# Sheet1_MB.net
KiCad netlist of a schematic drawn in Altium Designer
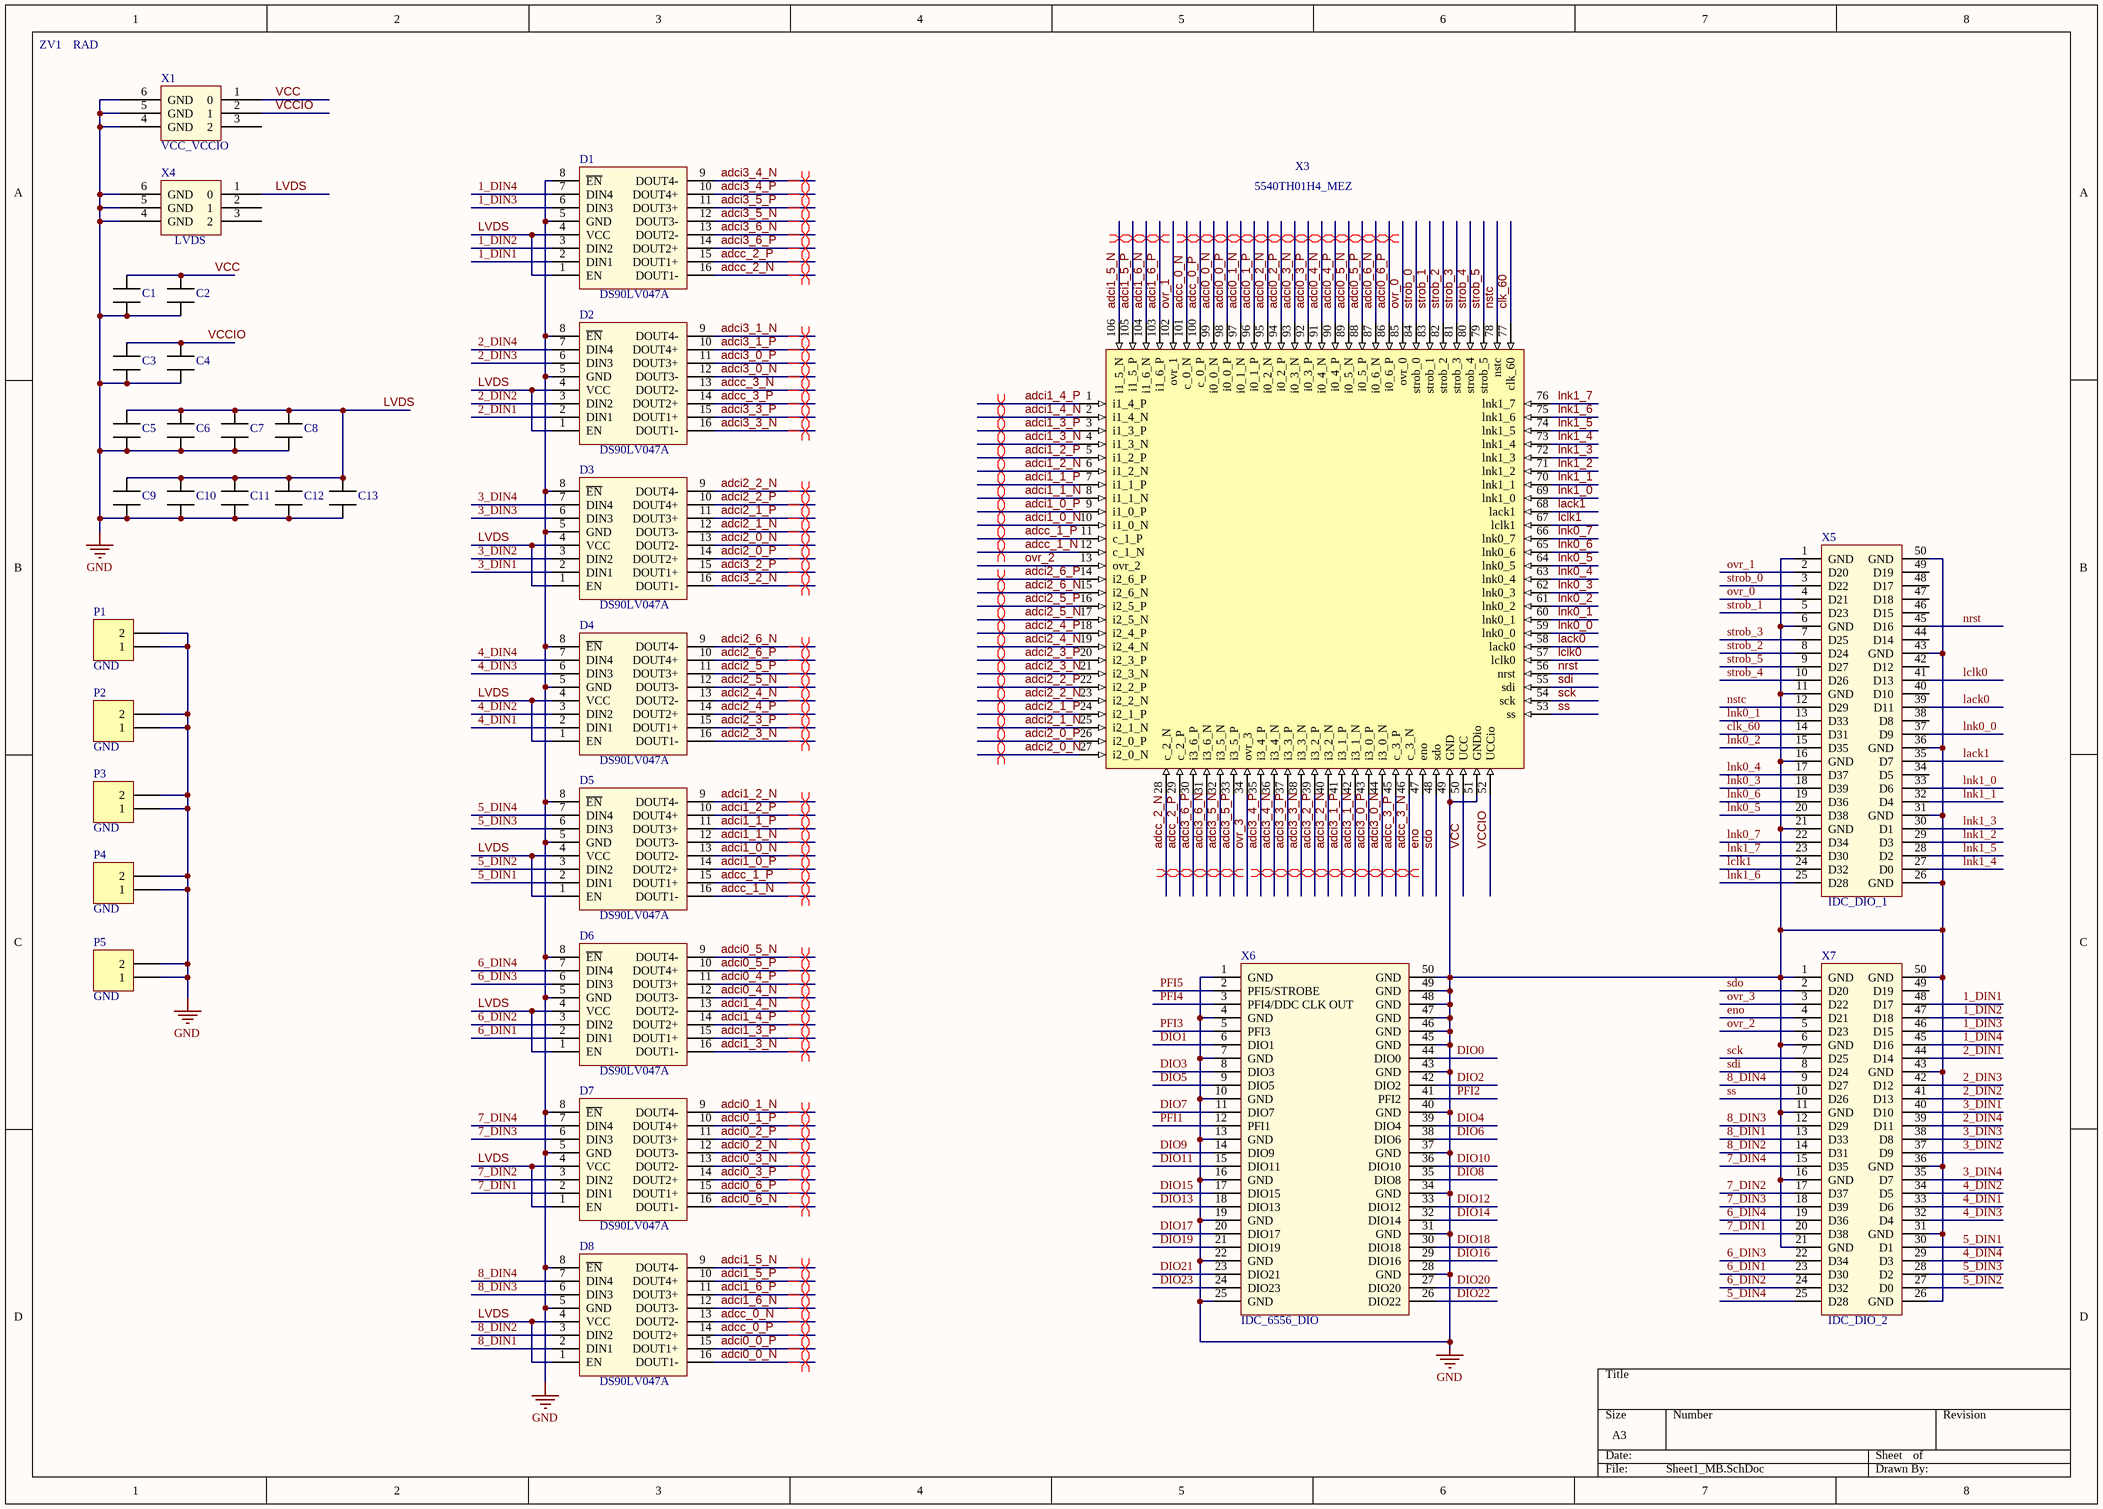
[diagram p0: Sheet1_MB.SchDoc]

(export (version "E")
  (design (tool "Eeschema 10.0.6"))
  (components
    (comp (ref "C1") (value "CAP_BIG") (footprint "Cap_BIG") (libsource (lib "Schlib") (part "CAP_BIG")))
    (comp (ref "C2")
      (value "CAP_SMALL")
      (footprint "CAP_SMALL")
      (libsource (lib "Schlib") (part "CAP_SMALL"))
    )
    (comp (ref "C3") (value "CAP_BIG") (footprint "Cap_BIG") (libsource (lib "Schlib") (part "CAP_BIG")))
    (comp (ref "C4")
      (value "CAP_SMALL")
      (footprint "CAP_SMALL")
      (libsource (lib "Schlib") (part "CAP_SMALL"))
    )
    (comp (ref "C5") (value "CAP_BIG") (footprint "Cap_BIG") (libsource (lib "Schlib") (part "CAP_BIG")))
    (comp (ref "C6")
      (value "CAP_SMALL")
      (footprint "CAP_SMALL")
      (libsource (lib "Schlib") (part "CAP_SMALL"))
    )
    (comp (ref "C7")
      (value "CAP_SMALL")
      (footprint "CAP_SMALL")
      (libsource (lib "Schlib") (part "CAP_SMALL"))
    )
    (comp (ref "C8")
      (value "CAP_SMALL")
      (footprint "CAP_SMALL")
      (libsource (lib "Schlib") (part "CAP_SMALL"))
    )
    (comp (ref "C9")
      (value "CAP_SMALL")
      (footprint "CAP_SMALL")
      (libsource (lib "Schlib") (part "CAP_SMALL"))
    )
    (comp (ref "C10")
      (value "CAP_SMALL")
      (footprint "CAP_SMALL")
      (libsource (lib "Schlib") (part "CAP_SMALL"))
    )
    (comp (ref "C11")
      (value "CAP_SMALL")
      (footprint "CAP_SMALL")
      (libsource (lib "Schlib") (part "CAP_SMALL"))
    )
    (comp (ref "C12")
      (value "CAP_SMALL")
      (footprint "CAP_SMALL")
      (libsource (lib "Schlib") (part "CAP_SMALL"))
    )
    (comp (ref "C13")
      (value "CAP_SMALL")
      (footprint "CAP_SMALL")
      (libsource (lib "Schlib") (part "CAP_SMALL"))
    )
    (comp (ref "D1")
      (value "DS90LV047A")
      (footprint "TSOP65P640X120-16N")
      (libsource (lib "Schlib") (part "DS90LV047A"))
    )
    (comp (ref "D2")
      (value "DS90LV047A")
      (footprint "TSOP65P640X120-16N")
      (libsource (lib "Schlib") (part "DS90LV047A"))
    )
    (comp (ref "D3")
      (value "DS90LV047A")
      (footprint "TSOP65P640X120-16N")
      (libsource (lib "Schlib") (part "DS90LV047A"))
    )
    (comp (ref "D4")
      (value "DS90LV047A")
      (footprint "TSOP65P640X120-16N")
      (libsource (lib "Schlib") (part "DS90LV047A"))
    )
    (comp (ref "D5")
      (value "DS90LV047A")
      (footprint "TSOP65P640X120-16N")
      (libsource (lib "Schlib") (part "DS90LV047A"))
    )
    (comp (ref "D6")
      (value "DS90LV047A")
      (footprint "TSOP65P640X120-16N")
      (libsource (lib "Schlib") (part "DS90LV047A"))
    )
    (comp (ref "D7")
      (value "DS90LV047A")
      (footprint "TSOP65P640X120-16N")
      (libsource (lib "Schlib") (part "DS90LV047A"))
    )
    (comp (ref "D8")
      (value "DS90LV047A")
      (footprint "TSOP65P640X120-16N")
      (libsource (lib "Schlib") (part "DS90LV047A"))
    )
    (comp (ref "P1")
      (value "GND")
      (footprint "HDR1X2")
      (description "Header, 2-Pin")
      (fields (field (name "PUBLISHER") "Altium Limited"))
      (libsource (lib "Miscellaneous Connectors") (part "Header 2"))
    )
    (comp (ref "P2")
      (value "GND")
      (footprint "HDR1X2")
      (description "Header, 2-Pin")
      (fields (field (name "PUBLISHER") "Altium Limited"))
      (libsource (lib "Miscellaneous Connectors") (part "Header 2"))
    )
    (comp (ref "P3")
      (value "GND")
      (footprint "HDR1X2")
      (description "Header, 2-Pin")
      (fields (field (name "PUBLISHER") "Altium Limited"))
      (libsource (lib "Miscellaneous Connectors") (part "Header 2"))
    )
    (comp (ref "P4")
      (value "GND")
      (footprint "HDR1X2")
      (description "Header, 2-Pin")
      (fields (field (name "PUBLISHER") "Altium Limited"))
      (libsource (lib "Miscellaneous Connectors") (part "Header 2"))
    )
    (comp (ref "P5")
      (value "GND")
      (footprint "HDR1X2")
      (description "Header, 2-Pin")
      (fields (field (name "PUBLISHER") "Altium Limited"))
      (libsource (lib "Miscellaneous Connectors") (part "Header 2"))
    )
    (comp (ref "X1") (value "VCC_VCCIO") (footprint "POWER") (libsource (lib "Schlib") (part "POWER")))
    (comp (ref "X3")
      (value "5540TH01H4_MEZ")
      (footprint "5540TH01H4_MEZ")
      (libsource (lib "VPL") (part "5540TH01H4_MEZ"))
    )
    (comp (ref "X4") (value "LVDS") (footprint "POWER") (libsource (lib "Schlib") (part "POWER")))
    (comp (ref "X5") (value "IDC_DIO_1") (footprint "IDC_DIO") (libsource (lib "VPL") (part "IDC_DIO")))
    (comp (ref "X6")
      (value "IDC_6556_DIO")
      (footprint "IDC_6556_DIO")
      (libsource (lib "VPL") (part "IDC_6556_DIO"))
    )
    (comp (ref "X7") (value "IDC_DIO_2") (footprint "IDC_DIO") (libsource (lib "VPL") (part "IDC_DIO")))
    (comp (ref "ZV1") (value "RAD") (footprint "RADIATION") (libsource (lib "VPL") (part "Radiation")))
  )
  (nets
    (net (code "1") (name "/1_DIN1") (class "Default")
      (node (ref "D1") (pin "2") (pinfunction "DIN1_2") (pintype "passive"))
      (node (ref "X7") (pin "48") (pinfunction "D17_48") (pintype "passive"))
    )
    (net (code "2") (name "/1_DIN2") (class "Default")
      (node (ref "D1") (pin "3") (pinfunction "DIN2_3") (pintype "passive"))
      (node (ref "X7") (pin "47") (pinfunction "D18_47") (pintype "passive"))
    )
    (net (code "3") (name "/1_DIN3") (class "Default")
      (node (ref "D1") (pin "6") (pinfunction "DIN3_6") (pintype "passive"))
      (node (ref "X7") (pin "46") (pinfunction "D15_46") (pintype "passive"))
    )
    (net (code "4") (name "/1_DIN4") (class "Default")
      (node (ref "D1") (pin "7") (pinfunction "DIN4_7") (pintype "passive"))
      (node (ref "X7") (pin "45") (pinfunction "D16_45") (pintype "passive"))
    )
    (net (code "5") (name "/2_DIN1") (class "Default")
      (node (ref "D2") (pin "2") (pinfunction "DIN1_2") (pintype "passive"))
      (node (ref "X7") (pin "44") (pinfunction "D14_44") (pintype "passive"))
    )
    (net (code "6") (name "/2_DIN2") (class "Default")
      (node (ref "D2") (pin "3") (pinfunction "DIN2_3") (pintype "passive"))
      (node (ref "X7") (pin "41") (pinfunction "D13_41") (pintype "passive"))
    )
    (net (code "7") (name "/2_DIN3") (class "Default")
      (node (ref "D2") (pin "6") (pinfunction "DIN3_6") (pintype "passive"))
      (node (ref "X7") (pin "42") (pinfunction "D12_42") (pintype "passive"))
    )
    (net (code "8") (name "/2_DIN4") (class "Default")
      (node (ref "D2") (pin "7") (pinfunction "DIN4_7") (pintype "passive"))
      (node (ref "X7") (pin "39") (pinfunction "D11_39") (pintype "passive"))
    )
    (net (code "9") (name "/3_DIN1") (class "Default")
      (node (ref "D3") (pin "2") (pinfunction "DIN1_2") (pintype "passive"))
      (node (ref "X7") (pin "40") (pinfunction "D10_40") (pintype "passive"))
    )
    (net (code "10") (name "/3_DIN2") (class "Default")
      (node (ref "D3") (pin "3") (pinfunction "DIN2_3") (pintype "passive"))
      (node (ref "X7") (pin "37") (pinfunction "D9_37") (pintype "passive"))
    )
    (net (code "11") (name "/3_DIN3") (class "Default")
      (node (ref "D3") (pin "6") (pinfunction "DIN3_6") (pintype "passive"))
      (node (ref "X7") (pin "38") (pinfunction "D8_38") (pintype "passive"))
    )
    (net (code "12") (name "/3_DIN4") (class "Default")
      (node (ref "D3") (pin "7") (pinfunction "DIN4_7") (pintype "passive"))
      (node (ref "X7") (pin "35") (pinfunction "D7_35") (pintype "passive"))
    )
    (net (code "13") (name "/4_DIN1") (class "Default")
      (node (ref "D4") (pin "2") (pinfunction "DIN1_2") (pintype "passive"))
      (node (ref "X7") (pin "33") (pinfunction "D6_33") (pintype "passive"))
    )
    (net (code "14") (name "/4_DIN2") (class "Default")
      (node (ref "D4") (pin "3") (pinfunction "DIN2_3") (pintype "passive"))
      (node (ref "X7") (pin "34") (pinfunction "D5_34") (pintype "passive"))
    )
    (net (code "15") (name "/4_DIN3") (class "Default")
      (node (ref "D4") (pin "6") (pinfunction "DIN3_6") (pintype "passive"))
      (node (ref "X7") (pin "32") (pinfunction "D4_32") (pintype "passive"))
    )
    (net (code "16") (name "/4_DIN4") (class "Default")
      (node (ref "D4") (pin "7") (pinfunction "DIN4_7") (pintype "passive"))
      (node (ref "X7") (pin "29") (pinfunction "D3_29") (pintype "passive"))
    )
    (net (code "17") (name "/5_DIN1") (class "Default")
      (node (ref "D5") (pin "2") (pinfunction "DIN1_2") (pintype "passive"))
      (node (ref "X7") (pin "30") (pinfunction "D1_30") (pintype "passive"))
    )
    (net (code "18") (name "/5_DIN2") (class "Default")
      (node (ref "D5") (pin "3") (pinfunction "DIN2_3") (pintype "passive"))
      (node (ref "X7") (pin "27") (pinfunction "D0_27") (pintype "passive"))
    )
    (net (code "19") (name "/5_DIN3") (class "Default")
      (node (ref "D5") (pin "6") (pinfunction "DIN3_6") (pintype "passive"))
      (node (ref "X7") (pin "28") (pinfunction "D2_28") (pintype "passive"))
    )
    (net (code "20") (name "/5_DIN4") (class "Default")
      (node (ref "D5") (pin "7") (pinfunction "DIN4_7") (pintype "passive"))
      (node (ref "X7") (pin "25") (pinfunction "D28_25") (pintype "passive"))
    )
    (net (code "21") (name "/6_DIN1") (class "Default")
      (node (ref "D6") (pin "2") (pinfunction "DIN1_2") (pintype "passive"))
      (node (ref "X7") (pin "23") (pinfunction "D30_23") (pintype "passive"))
    )
    (net (code "22") (name "/6_DIN2") (class "Default")
      (node (ref "D6") (pin "3") (pinfunction "DIN2_3") (pintype "passive"))
      (node (ref "X7") (pin "24") (pinfunction "D32_24") (pintype "passive"))
    )
    (net (code "23") (name "/6_DIN3") (class "Default")
      (node (ref "D6") (pin "6") (pinfunction "DIN3_6") (pintype "passive"))
      (node (ref "X7") (pin "22") (pinfunction "D34_22") (pintype "passive"))
    )
    (net (code "24") (name "/6_DIN4") (class "Default")
      (node (ref "D6") (pin "7") (pinfunction "DIN4_7") (pintype "passive"))
      (node (ref "X7") (pin "19") (pinfunction "D36_19") (pintype "passive"))
    )
    (net (code "25") (name "/7_DIN1") (class "Default")
      (node (ref "D7") (pin "2") (pinfunction "DIN1_2") (pintype "passive"))
      (node (ref "X7") (pin "20") (pinfunction "D38_20") (pintype "passive"))
    )
    (net (code "26") (name "/7_DIN2") (class "Default")
      (node (ref "D7") (pin "3") (pinfunction "DIN2_3") (pintype "passive"))
      (node (ref "X7") (pin "17") (pinfunction "D37_17") (pintype "passive"))
    )
    (net (code "27") (name "/7_DIN3") (class "Default")
      (node (ref "D7") (pin "6") (pinfunction "DIN3_6") (pintype "passive"))
      (node (ref "X7") (pin "18") (pinfunction "D39_18") (pintype "passive"))
    )
    (net (code "28") (name "/7_DIN4") (class "Default")
      (node (ref "D7") (pin "7") (pinfunction "DIN4_7") (pintype "passive"))
      (node (ref "X7") (pin "15") (pinfunction "D35_15") (pintype "passive"))
    )
    (net (code "29") (name "/8_DIN1") (class "Default")
      (node (ref "D8") (pin "2") (pinfunction "DIN1_2") (pintype "passive"))
      (node (ref "X7") (pin "13") (pinfunction "D33_13") (pintype "passive"))
    )
    (net (code "30") (name "/8_DIN2") (class "Default")
      (node (ref "D8") (pin "3") (pinfunction "DIN2_3") (pintype "passive"))
      (node (ref "X7") (pin "14") (pinfunction "D31_14") (pintype "passive"))
    )
    (net (code "31") (name "/8_DIN3") (class "Default")
      (node (ref "D8") (pin "6") (pinfunction "DIN3_6") (pintype "passive"))
      (node (ref "X7") (pin "12") (pinfunction "D29_12") (pintype "passive"))
    )
    (net (code "32") (name "/8_DIN4") (class "Default")
      (node (ref "D8") (pin "7") (pinfunction "DIN4_7") (pintype "passive"))
      (node (ref "X7") (pin "9") (pinfunction "D27_9") (pintype "passive"))
    )
    (net (code "33") (name "/DIO0") (class "Default")
      (node (ref "X6") (pin "44") (pinfunction "DIO0_44") (pintype "passive"))
    )
    (net (code "34") (name "/DIO1") (class "Default")
      (node (ref "X6") (pin "6") (pinfunction "DIO1_6") (pintype "passive"))
    )
    (net (code "35") (name "/DIO2") (class "Default")
      (node (ref "X6") (pin "42") (pinfunction "DIO2_42") (pintype "passive"))
    )
    (net (code "36") (name "/DIO3") (class "Default")
      (node (ref "X6") (pin "8") (pinfunction "DIO3_8") (pintype "passive"))
    )
    (net (code "37") (name "/DIO4") (class "Default")
      (node (ref "X6") (pin "39") (pinfunction "DIO4_39") (pintype "passive"))
    )
    (net (code "38") (name "/DIO5") (class "Default")
      (node (ref "X6") (pin "9") (pinfunction "DIO5_9") (pintype "passive"))
    )
    (net (code "39") (name "/DIO6") (class "Default")
      (node (ref "X6") (pin "38") (pinfunction "DIO6_38") (pintype "passive"))
    )
    (net (code "40") (name "/DIO7") (class "Default")
      (node (ref "X6") (pin "11") (pinfunction "DIO7_11") (pintype "passive"))
    )
    (net (code "41") (name "/DIO8") (class "Default")
      (node (ref "X6") (pin "35") (pinfunction "DIO8_35") (pintype "passive"))
    )
    (net (code "42") (name "/DIO9") (class "Default")
      (node (ref "X6") (pin "14") (pinfunction "DIO9_14") (pintype "passive"))
    )
    (net (code "43") (name "/DIO10") (class "Default")
      (node (ref "X6") (pin "36") (pinfunction "DIO10_36") (pintype "passive"))
    )
    (net (code "44") (name "/DIO11") (class "Default")
      (node (ref "X6") (pin "15") (pinfunction "DIO11_15") (pintype "passive"))
    )
    (net (code "45") (name "/DIO12") (class "Default")
      (node (ref "X6") (pin "33") (pinfunction "DIO12_33") (pintype "passive"))
    )
    (net (code "46") (name "/DIO13") (class "Default")
      (node (ref "X6") (pin "18") (pinfunction "DIO13_18") (pintype "passive"))
    )
    (net (code "47") (name "/DIO14") (class "Default")
      (node (ref "X6") (pin "32") (pinfunction "DIO14_32") (pintype "passive"))
    )
    (net (code "48") (name "/DIO15") (class "Default")
      (node (ref "X6") (pin "17") (pinfunction "DIO15_17") (pintype "passive"))
    )
    (net (code "49") (name "/DIO16") (class "Default")
      (node (ref "X6") (pin "29") (pinfunction "DIO16_29") (pintype "passive"))
    )
    (net (code "50") (name "/DIO17") (class "Default")
      (node (ref "X6") (pin "20") (pinfunction "DIO17_20") (pintype "passive"))
    )
    (net (code "51") (name "/DIO18") (class "Default")
      (node (ref "X6") (pin "30") (pinfunction "DIO18_30") (pintype "passive"))
    )
    (net (code "52") (name "/DIO19") (class "Default")
      (node (ref "X6") (pin "21") (pinfunction "DIO19_21") (pintype "passive"))
    )
    (net (code "53") (name "/DIO20") (class "Default")
      (node (ref "X6") (pin "27") (pinfunction "DIO20_27") (pintype "passive"))
    )
    (net (code "54") (name "/DIO21") (class "Default")
      (node (ref "X6") (pin "23") (pinfunction "DIO21_23") (pintype "passive"))
    )
    (net (code "55") (name "/DIO22") (class "Default")
      (node (ref "X6") (pin "26") (pinfunction "DIO22_26") (pintype "passive"))
    )
    (net (code "56") (name "/DIO23") (class "Default")
      (node (ref "X6") (pin "24") (pinfunction "DIO23_24") (pintype "passive"))
    )
    (net (code "57") (name "/LVDS") (class "Default")
      (node (ref "C10") (pin "2") (pinfunction "2_2") (pintype "passive"))
      (node (ref "C11") (pin "2") (pinfunction "2_2") (pintype "passive"))
      (node (ref "C12") (pin "2") (pinfunction "2_2") (pintype "passive"))
      (node (ref "C13") (pin "2") (pinfunction "2_2") (pintype "passive"))
      (node (ref "C5") (pin "2") (pinfunction "2_2") (pintype "passive"))
      (node (ref "C6") (pin "2") (pinfunction "2_2") (pintype "passive"))
      (node (ref "C7") (pin "2") (pinfunction "2_2") (pintype "passive"))
      (node (ref "C8") (pin "2") (pinfunction "2_2") (pintype "passive"))
      (node (ref "C9") (pin "2") (pinfunction "2_2") (pintype "passive"))
      (node (ref "D1") (pin "1") (pinfunction "EN_1") (pintype "passive"))
      (node (ref "D1") (pin "4") (pinfunction "VCC_4") (pintype "passive"))
      (node (ref "D2") (pin "1") (pinfunction "EN_1") (pintype "passive"))
      (node (ref "D2") (pin "4") (pinfunction "VCC_4") (pintype "passive"))
      (node (ref "D3") (pin "1") (pinfunction "EN_1") (pintype "passive"))
      (node (ref "D3") (pin "4") (pinfunction "VCC_4") (pintype "passive"))
      (node (ref "D4") (pin "1") (pinfunction "EN_1") (pintype "passive"))
      (node (ref "D4") (pin "4") (pinfunction "VCC_4") (pintype "passive"))
      (node (ref "D5") (pin "1") (pinfunction "EN_1") (pintype "passive"))
      (node (ref "D5") (pin "4") (pinfunction "VCC_4") (pintype "passive"))
      (node (ref "D6") (pin "1") (pinfunction "EN_1") (pintype "passive"))
      (node (ref "D6") (pin "4") (pinfunction "VCC_4") (pintype "passive"))
      (node (ref "D7") (pin "1") (pinfunction "EN_1") (pintype "passive"))
      (node (ref "D7") (pin "4") (pinfunction "VCC_4") (pintype "passive"))
      (node (ref "D8") (pin "1") (pinfunction "EN_1") (pintype "passive"))
      (node (ref "D8") (pin "4") (pinfunction "VCC_4") (pintype "passive"))
      (node (ref "X4") (pin "1") (pinfunction "0_1") (pintype "passive"))
    )
    (net (code "58") (name "/PFI1") (class "Default")
      (node (ref "X6") (pin "12") (pinfunction "PFI1_12") (pintype "passive"))
    )
    (net (code "59") (name "/PFI2") (class "Default")
      (node (ref "X6") (pin "41") (pinfunction "PFI2_41") (pintype "passive"))
    )
    (net (code "60") (name "/PFI3") (class "Default")
      (node (ref "X6") (pin "5") (pinfunction "PFI3_5") (pintype "passive"))
    )
    (net (code "61") (name "/PFI4") (class "Default")
      (node (ref "X6") (pin "3") (pinfunction "PFI4/DDC_CLK_OUT_3") (pintype "passive"))
    )
    (net (code "62") (name "/PFI5") (class "Default")
      (node (ref "X6") (pin "2") (pinfunction "PFI5/STROBE_2") (pintype "passive"))
    )
    (net (code "63") (name "/VCC") (class "Default")
      (node (ref "C1") (pin "2") (pinfunction "2_2") (pintype "passive"))
      (node (ref "C2") (pin "2") (pinfunction "2_2") (pintype "passive"))
      (node (ref "X1") (pin "1") (pinfunction "0_1") (pintype "passive"))
      (node (ref "X3") (pin "50") (pinfunction "UCC_50") (pintype "input"))
    )
    (net (code "64") (name "/VCCIO") (class "Default")
      (node (ref "C3") (pin "2") (pinfunction "2_2") (pintype "passive"))
      (node (ref "C4") (pin "2") (pinfunction "2_2") (pintype "passive"))
      (node (ref "X1") (pin "2") (pinfunction "1_2") (pintype "passive"))
      (node (ref "X3") (pin "52") (pinfunction "UCCio_52") (pintype "input"))
    )
    (net (code "65") (name "/adcc_0_N") (class "Default")
      (node (ref "D8") (pin "13") (pinfunction "DOUT2-_13") (pintype "passive"))
      (node (ref "X3") (pin "101") (pinfunction "c_0_N_101") (pintype "input"))
    )
    (net (code "66") (name "/adcc_0_P") (class "Default")
      (node (ref "D8") (pin "14") (pinfunction "DOUT2+_14") (pintype "passive"))
      (node (ref "X3") (pin "100") (pinfunction "c_0_P_100") (pintype "input"))
    )
    (net (code "67") (name "/adcc_1_N") (class "Default")
      (node (ref "D5") (pin "16") (pinfunction "DOUT1-_16") (pintype "passive"))
      (node (ref "X3") (pin "12") (pinfunction "c_1_N_12") (pintype "input"))
    )
    (net (code "68") (name "/adcc_1_P") (class "Default")
      (node (ref "D5") (pin "15") (pinfunction "DOUT1+_15") (pintype "passive"))
      (node (ref "X3") (pin "11") (pinfunction "c_1_P_11") (pintype "input"))
    )
    (net (code "69") (name "/adcc_2_N") (class "Default")
      (node (ref "D1") (pin "16") (pinfunction "DOUT1-_16") (pintype "passive"))
      (node (ref "X3") (pin "28") (pinfunction "c_2_N_28") (pintype "input"))
    )
    (net (code "70") (name "/adcc_2_P") (class "Default")
      (node (ref "D1") (pin "15") (pinfunction "DOUT1+_15") (pintype "passive"))
      (node (ref "X3") (pin "29") (pinfunction "c_2_P_29") (pintype "input"))
    )
    (net (code "71") (name "/adcc_3_N") (class "Default")
      (node (ref "D2") (pin "13") (pinfunction "DOUT2-_13") (pintype "passive"))
      (node (ref "X3") (pin "46") (pinfunction "c_3_N_46") (pintype "input"))
    )
    (net (code "72") (name "/adcc_3_P") (class "Default")
      (node (ref "D2") (pin "14") (pinfunction "DOUT2+_14") (pintype "passive"))
      (node (ref "X3") (pin "45") (pinfunction "c_3_P_45") (pintype "input"))
    )
    (net (code "73") (name "/adci0_0_N") (class "Default")
      (node (ref "D8") (pin "16") (pinfunction "DOUT1-_16") (pintype "passive"))
      (node (ref "X3") (pin "99") (pinfunction "i0_0_N_99") (pintype "input"))
    )
    (net (code "74") (name "/adci0_0_P") (class "Default")
      (node (ref "D8") (pin "15") (pinfunction "DOUT1+_15") (pintype "passive"))
      (node (ref "X3") (pin "98") (pinfunction "i0_0_P_98") (pintype "input"))
    )
    (net (code "75") (name "/adci0_1_N") (class "Default")
      (node (ref "D7") (pin "9") (pinfunction "DOUT4-_9") (pintype "passive"))
      (node (ref "X3") (pin "97") (pinfunction "i0_1_N_97") (pintype "input"))
    )
    (net (code "76") (name "/adci0_1_P") (class "Default")
      (node (ref "D7") (pin "10") (pinfunction "DOUT4+_10") (pintype "passive"))
      (node (ref "X3") (pin "96") (pinfunction "i0_1_P_96") (pintype "input"))
    )
    (net (code "77") (name "/adci0_2_N") (class "Default")
      (node (ref "D7") (pin "12") (pinfunction "DOUT3-_12") (pintype "passive"))
      (node (ref "X3") (pin "95") (pinfunction "i0_2_N_95") (pintype "input"))
    )
    (net (code "78") (name "/adci0_2_P") (class "Default")
      (node (ref "D7") (pin "11") (pinfunction "DOUT3+_11") (pintype "passive"))
      (node (ref "X3") (pin "94") (pinfunction "i0_2_P_94") (pintype "input"))
    )
    (net (code "79") (name "/adci0_3_N") (class "Default")
      (node (ref "D7") (pin "13") (pinfunction "DOUT2-_13") (pintype "passive"))
      (node (ref "X3") (pin "93") (pinfunction "i0_3_N_93") (pintype "input"))
    )
    (net (code "80") (name "/adci0_3_P") (class "Default")
      (node (ref "D7") (pin "14") (pinfunction "DOUT2+_14") (pintype "passive"))
      (node (ref "X3") (pin "92") (pinfunction "i0_3_P_92") (pintype "input"))
    )
    (net (code "81") (name "/adci0_4_N") (class "Default")
      (node (ref "D6") (pin "12") (pinfunction "DOUT3-_12") (pintype "passive"))
      (node (ref "X3") (pin "91") (pinfunction "i0_4_N_91") (pintype "input"))
    )
    (net (code "82") (name "/adci0_4_P") (class "Default")
      (node (ref "D6") (pin "11") (pinfunction "DOUT3+_11") (pintype "passive"))
      (node (ref "X3") (pin "90") (pinfunction "i0_4_P_90") (pintype "input"))
    )
    (net (code "83") (name "/adci0_5_N") (class "Default")
      (node (ref "D6") (pin "9") (pinfunction "DOUT4-_9") (pintype "passive"))
      (node (ref "X3") (pin "89") (pinfunction "i0_5_N_89") (pintype "input"))
    )
    (net (code "84") (name "/adci0_5_P") (class "Default")
      (node (ref "D6") (pin "10") (pinfunction "DOUT4+_10") (pintype "passive"))
      (node (ref "X3") (pin "88") (pinfunction "i0_5_P_88") (pintype "input"))
    )
    (net (code "85") (name "/adci0_6_N") (class "Default")
      (node (ref "D7") (pin "16") (pinfunction "DOUT1-_16") (pintype "passive"))
      (node (ref "X3") (pin "87") (pinfunction "i0_6_N_87") (pintype "input"))
    )
    (net (code "86") (name "/adci0_6_P") (class "Default")
      (node (ref "D7") (pin "15") (pinfunction "DOUT1+_15") (pintype "passive"))
      (node (ref "X3") (pin "86") (pinfunction "i0_6_P_86") (pintype "input"))
    )
    (net (code "87") (name "/adci1_0_N") (class "Default")
      (node (ref "D5") (pin "13") (pinfunction "DOUT2-_13") (pintype "passive"))
      (node (ref "X3") (pin "10") (pinfunction "i1_0_N_10") (pintype "input"))
    )
    (net (code "88") (name "/adci1_0_P") (class "Default")
      (node (ref "D5") (pin "14") (pinfunction "DOUT2+_14") (pintype "passive"))
      (node (ref "X3") (pin "9") (pinfunction "i1_0_P_9") (pintype "input"))
    )
    (net (code "89") (name "/adci1_1_N") (class "Default")
      (node (ref "D5") (pin "12") (pinfunction "DOUT3-_12") (pintype "passive"))
      (node (ref "X3") (pin "8") (pinfunction "i1_1_N_8") (pintype "input"))
    )
    (net (code "90") (name "/adci1_1_P") (class "Default")
      (node (ref "D5") (pin "11") (pinfunction "DOUT3+_11") (pintype "passive"))
      (node (ref "X3") (pin "7") (pinfunction "i1_1_P_7") (pintype "input"))
    )
    (net (code "91") (name "/adci1_2_N") (class "Default")
      (node (ref "D5") (pin "9") (pinfunction "DOUT4-_9") (pintype "passive"))
      (node (ref "X3") (pin "6") (pinfunction "i1_2_N_6") (pintype "input"))
    )
    (net (code "92") (name "/adci1_2_P") (class "Default")
      (node (ref "D5") (pin "10") (pinfunction "DOUT4+_10") (pintype "passive"))
      (node (ref "X3") (pin "5") (pinfunction "i1_2_P_5") (pintype "input"))
    )
    (net (code "93") (name "/adci1_3_N") (class "Default")
      (node (ref "D6") (pin "16") (pinfunction "DOUT1-_16") (pintype "passive"))
      (node (ref "X3") (pin "4") (pinfunction "i1_3_N_4") (pintype "input"))
    )
    (net (code "94") (name "/adci1_3_P") (class "Default")
      (node (ref "D6") (pin "15") (pinfunction "DOUT1+_15") (pintype "passive"))
      (node (ref "X3") (pin "3") (pinfunction "i1_3_P_3") (pintype "input"))
    )
    (net (code "95") (name "/adci1_4_N") (class "Default")
      (node (ref "D6") (pin "13") (pinfunction "DOUT2-_13") (pintype "passive"))
      (node (ref "X3") (pin "2") (pinfunction "i1_4_N_2") (pintype "input"))
    )
    (net (code "96") (name "/adci1_4_P") (class "Default")
      (node (ref "D6") (pin "14") (pinfunction "DOUT2+_14") (pintype "passive"))
      (node (ref "X3") (pin "1") (pinfunction "i1_4_P_1") (pintype "input"))
    )
    (net (code "97") (name "/adci1_5_N") (class "Default")
      (node (ref "D8") (pin "9") (pinfunction "DOUT4-_9") (pintype "passive"))
      (node (ref "X3") (pin "106") (pinfunction "i1_5_N_106") (pintype "input"))
    )
    (net (code "98") (name "/adci1_5_P") (class "Default")
      (node (ref "D8") (pin "10") (pinfunction "DOUT4+_10") (pintype "passive"))
      (node (ref "X3") (pin "105") (pinfunction "i1_5_P_105") (pintype "input"))
    )
    (net (code "99") (name "/adci1_6_N") (class "Default")
      (node (ref "D8") (pin "12") (pinfunction "DOUT3-_12") (pintype "passive"))
      (node (ref "X3") (pin "104") (pinfunction "i1_6_N_104") (pintype "input"))
    )
    (net (code "100") (name "/adci1_6_P") (class "Default")
      (node (ref "D8") (pin "11") (pinfunction "DOUT3+_11") (pintype "passive"))
      (node (ref "X3") (pin "103") (pinfunction "i1_6_P_103") (pintype "input"))
    )
    (net (code "101") (name "/adci2_0_N") (class "Default")
      (node (ref "D3") (pin "13") (pinfunction "DOUT2-_13") (pintype "passive"))
      (node (ref "X3") (pin "27") (pinfunction "i2_0_N_27") (pintype "input"))
    )
    (net (code "102") (name "/adci2_0_P") (class "Default")
      (node (ref "D3") (pin "14") (pinfunction "DOUT2+_14") (pintype "passive"))
      (node (ref "X3") (pin "26") (pinfunction "i2_0_P_26") (pintype "input"))
    )
    (net (code "103") (name "/adci2_1_N") (class "Default")
      (node (ref "D3") (pin "12") (pinfunction "DOUT3-_12") (pintype "passive"))
      (node (ref "X3") (pin "25") (pinfunction "i2_1_N_25") (pintype "input"))
    )
    (net (code "104") (name "/adci2_1_P") (class "Default")
      (node (ref "D3") (pin "11") (pinfunction "DOUT3+_11") (pintype "passive"))
      (node (ref "X3") (pin "24") (pinfunction "i2_1_P_24") (pintype "input"))
    )
    (net (code "105") (name "/adci2_2_N") (class "Default")
      (node (ref "D3") (pin "9") (pinfunction "DOUT4-_9") (pintype "passive"))
      (node (ref "X3") (pin "23") (pinfunction "i2_2_N_23") (pintype "input"))
    )
    (net (code "106") (name "/adci2_2_P") (class "Default")
      (node (ref "D3") (pin "10") (pinfunction "DOUT4+_10") (pintype "passive"))
      (node (ref "X3") (pin "22") (pinfunction "i2_2_P_22") (pintype "input"))
    )
    (net (code "107") (name "/adci2_3_N") (class "Default")
      (node (ref "D4") (pin "16") (pinfunction "DOUT1-_16") (pintype "passive"))
      (node (ref "X3") (pin "21") (pinfunction "i2_3_N_21") (pintype "input"))
    )
    (net (code "108") (name "/adci2_3_P") (class "Default")
      (node (ref "D4") (pin "15") (pinfunction "DOUT1+_15") (pintype "passive"))
      (node (ref "X3") (pin "20") (pinfunction "i2_3_P_20") (pintype "input"))
    )
    (net (code "109") (name "/adci2_4_N") (class "Default")
      (node (ref "D4") (pin "13") (pinfunction "DOUT2-_13") (pintype "passive"))
      (node (ref "X3") (pin "19") (pinfunction "i2_4_N_19") (pintype "input"))
    )
    (net (code "110") (name "/adci2_4_P") (class "Default")
      (node (ref "D4") (pin "14") (pinfunction "DOUT2+_14") (pintype "passive"))
      (node (ref "X3") (pin "18") (pinfunction "i2_4_P_18") (pintype "input"))
    )
    (net (code "111") (name "/adci2_5_N") (class "Default")
      (node (ref "D4") (pin "12") (pinfunction "DOUT3-_12") (pintype "passive"))
      (node (ref "X3") (pin "17") (pinfunction "i2_5_N_17") (pintype "input"))
    )
    (net (code "112") (name "/adci2_5_P") (class "Default")
      (node (ref "D4") (pin "11") (pinfunction "DOUT3+_11") (pintype "passive"))
      (node (ref "X3") (pin "16") (pinfunction "i2_5_P_16") (pintype "input"))
    )
    (net (code "113") (name "/adci2_6_N") (class "Default")
      (node (ref "D4") (pin "9") (pinfunction "DOUT4-_9") (pintype "passive"))
      (node (ref "X3") (pin "15") (pinfunction "i2_6_N_15") (pintype "input"))
    )
    (net (code "114") (name "/adci2_6_P") (class "Default")
      (node (ref "D4") (pin "10") (pinfunction "DOUT4+_10") (pintype "passive"))
      (node (ref "X3") (pin "14") (pinfunction "i2_6_P_14") (pintype "input"))
    )
    (net (code "115") (name "/adci3_0_N") (class "Default")
      (node (ref "D2") (pin "12") (pinfunction "DOUT3-_12") (pintype "passive"))
      (node (ref "X3") (pin "44") (pinfunction "i3_0_N_44") (pintype "input"))
    )
    (net (code "116") (name "/adci3_0_P") (class "Default")
      (node (ref "D2") (pin "11") (pinfunction "DOUT3+_11") (pintype "passive"))
      (node (ref "X3") (pin "43") (pinfunction "i3_0_P_43") (pintype "input"))
    )
    (net (code "117") (name "/adci3_1_N") (class "Default")
      (node (ref "D2") (pin "9") (pinfunction "DOUT4-_9") (pintype "passive"))
      (node (ref "X3") (pin "42") (pinfunction "i3_1_N_42") (pintype "input"))
    )
    (net (code "118") (name "/adci3_1_P") (class "Default")
      (node (ref "D2") (pin "10") (pinfunction "DOUT4+_10") (pintype "passive"))
      (node (ref "X3") (pin "41") (pinfunction "i3_1_P_41") (pintype "input"))
    )
    (net (code "119") (name "/adci3_2_N") (class "Default")
      (node (ref "D3") (pin "16") (pinfunction "DOUT1-_16") (pintype "passive"))
      (node (ref "X3") (pin "40") (pinfunction "i3_2_N_40") (pintype "input"))
    )
    (net (code "120") (name "/adci3_2_P") (class "Default")
      (node (ref "D3") (pin "15") (pinfunction "DOUT1+_15") (pintype "passive"))
      (node (ref "X3") (pin "39") (pinfunction "i3_2_P_39") (pintype "input"))
    )
    (net (code "121") (name "/adci3_3_N") (class "Default")
      (node (ref "D2") (pin "16") (pinfunction "DOUT1-_16") (pintype "passive"))
      (node (ref "X3") (pin "38") (pinfunction "i3_3_N_38") (pintype "input"))
    )
    (net (code "122") (name "/adci3_3_P") (class "Default")
      (node (ref "D2") (pin "15") (pinfunction "DOUT1+_15") (pintype "passive"))
      (node (ref "X3") (pin "37") (pinfunction "i3_3_P_37") (pintype "input"))
    )
    (net (code "123") (name "/adci3_4_N") (class "Default")
      (node (ref "D1") (pin "9") (pinfunction "DOUT4-_9") (pintype "passive"))
      (node (ref "X3") (pin "36") (pinfunction "i3_4_N_36") (pintype "input"))
    )
    (net (code "124") (name "/adci3_4_P") (class "Default")
      (node (ref "D1") (pin "10") (pinfunction "DOUT4+_10") (pintype "passive"))
      (node (ref "X3") (pin "35") (pinfunction "i3_4_P_35") (pintype "input"))
    )
    (net (code "125") (name "/adci3_5_N") (class "Default")
      (node (ref "D1") (pin "12") (pinfunction "DOUT3-_12") (pintype "passive"))
      (node (ref "X3") (pin "32") (pinfunction "i3_5_N_32") (pintype "input"))
    )
    (net (code "126") (name "/adci3_5_P") (class "Default")
      (node (ref "D1") (pin "11") (pinfunction "DOUT3+_11") (pintype "passive"))
      (node (ref "X3") (pin "33") (pinfunction "i3_5_P_33") (pintype "input"))
    )
    (net (code "127") (name "/adci3_6_N") (class "Default")
      (node (ref "D1") (pin "13") (pinfunction "DOUT2-_13") (pintype "passive"))
      (node (ref "X3") (pin "31") (pinfunction "i3_6_N_31") (pintype "input"))
    )
    (net (code "128") (name "/adci3_6_P") (class "Default")
      (node (ref "D1") (pin "14") (pinfunction "DOUT2+_14") (pintype "passive"))
      (node (ref "X3") (pin "30") (pinfunction "i3_6_P_30") (pintype "input"))
    )
    (net (code "129") (name "/clk_60") (class "Default")
      (node (ref "X3") (pin "77") (pinfunction "clk_60_77") (pintype "input"))
      (node (ref "X5") (pin "14") (pinfunction "D31_14") (pintype "passive"))
    )
    (net (code "130") (name "/eno") (class "Default")
      (node (ref "X3") (pin "47") (pinfunction "eno_47") (pintype "input"))
      (node (ref "X7") (pin "4") (pinfunction "D21_4") (pintype "passive"))
    )
    (net (code "131") (name "/lack0") (class "Default")
      (node (ref "X3") (pin "58") (pinfunction "lack0_58") (pintype "input"))
      (node (ref "X5") (pin "39") (pinfunction "D11_39") (pintype "passive"))
    )
    (net (code "132") (name "/lack1") (class "Default")
      (node (ref "X3") (pin "68") (pinfunction "lack1_68") (pintype "input"))
      (node (ref "X5") (pin "35") (pinfunction "D7_35") (pintype "passive"))
    )
    (net (code "133") (name "/lclk0") (class "Default")
      (node (ref "X3") (pin "57") (pinfunction "lclk0_57") (pintype "input"))
      (node (ref "X5") (pin "41") (pinfunction "D13_41") (pintype "passive"))
    )
    (net (code "134") (name "/lclk1") (class "Default")
      (node (ref "X3") (pin "67") (pinfunction "lclk1_67") (pintype "input"))
      (node (ref "X5") (pin "24") (pinfunction "D32_24") (pintype "passive"))
    )
    (net (code "135") (name "/lnk0_0") (class "Default")
      (node (ref "X3") (pin "59") (pinfunction "lnk0_0_59") (pintype "input"))
      (node (ref "X5") (pin "37") (pinfunction "D9_37") (pintype "passive"))
    )
    (net (code "136") (name "/lnk0_1") (class "Default")
      (node (ref "X3") (pin "60") (pinfunction "lnk0_1_60") (pintype "input"))
      (node (ref "X5") (pin "13") (pinfunction "D33_13") (pintype "passive"))
    )
    (net (code "137") (name "/lnk0_2") (class "Default")
      (node (ref "X3") (pin "61") (pinfunction "lnk0_2_61") (pintype "input"))
      (node (ref "X5") (pin "15") (pinfunction "D35_15") (pintype "passive"))
    )
    (net (code "138") (name "/lnk0_3") (class "Default")
      (node (ref "X3") (pin "62") (pinfunction "lnk0_3_62") (pintype "input"))
      (node (ref "X5") (pin "18") (pinfunction "D39_18") (pintype "passive"))
    )
    (net (code "139") (name "/lnk0_4") (class "Default")
      (node (ref "X3") (pin "63") (pinfunction "lnk0_4_63") (pintype "input"))
      (node (ref "X5") (pin "17") (pinfunction "D37_17") (pintype "passive"))
    )
    (net (code "140") (name "/lnk0_5") (class "Default")
      (node (ref "X3") (pin "64") (pinfunction "lnk0_5_64") (pintype "input"))
      (node (ref "X5") (pin "20") (pinfunction "D38_20") (pintype "passive"))
    )
    (net (code "141") (name "/lnk0_6") (class "Default")
      (node (ref "X3") (pin "65") (pinfunction "lnk0_6_65") (pintype "input"))
      (node (ref "X5") (pin "19") (pinfunction "D36_19") (pintype "passive"))
    )
    (net (code "142") (name "/lnk0_7") (class "Default")
      (node (ref "X3") (pin "66") (pinfunction "lnk0_7_66") (pintype "input"))
      (node (ref "X5") (pin "22") (pinfunction "D34_22") (pintype "passive"))
    )
    (net (code "143") (name "/lnk1_0") (class "Default")
      (node (ref "X3") (pin "69") (pinfunction "lnk1_0_69") (pintype "input"))
      (node (ref "X5") (pin "33") (pinfunction "D6_33") (pintype "passive"))
    )
    (net (code "144") (name "/lnk1_1") (class "Default")
      (node (ref "X3") (pin "70") (pinfunction "lnk1_1_70") (pintype "input"))
      (node (ref "X5") (pin "32") (pinfunction "D4_32") (pintype "passive"))
    )
    (net (code "145") (name "/lnk1_2") (class "Default")
      (node (ref "X3") (pin "71") (pinfunction "lnk1_2_71") (pintype "input"))
      (node (ref "X5") (pin "29") (pinfunction "D3_29") (pintype "passive"))
    )
    (net (code "146") (name "/lnk1_3") (class "Default")
      (node (ref "X3") (pin "72") (pinfunction "lnk1_3_72") (pintype "input"))
      (node (ref "X5") (pin "30") (pinfunction "D1_30") (pintype "passive"))
    )
    (net (code "147") (name "/lnk1_4") (class "Default")
      (node (ref "X3") (pin "73") (pinfunction "lnk1_4_73") (pintype "input"))
      (node (ref "X5") (pin "27") (pinfunction "D0_27") (pintype "passive"))
    )
    (net (code "148") (name "/lnk1_5") (class "Default")
      (node (ref "X3") (pin "74") (pinfunction "lnk1_5_74") (pintype "input"))
      (node (ref "X5") (pin "28") (pinfunction "D2_28") (pintype "passive"))
    )
    (net (code "149") (name "/lnk1_6") (class "Default")
      (node (ref "X3") (pin "75") (pinfunction "lnk1_6_75") (pintype "input"))
      (node (ref "X5") (pin "25") (pinfunction "D28_25") (pintype "passive"))
    )
    (net (code "150") (name "/lnk1_7") (class "Default")
      (node (ref "X3") (pin "76") (pinfunction "lnk1_7_76") (pintype "input"))
      (node (ref "X5") (pin "23") (pinfunction "D30_23") (pintype "passive"))
    )
    (net (code "151") (name "/nrst") (class "Default")
      (node (ref "X3") (pin "56") (pinfunction "nrst_56") (pintype "input"))
      (node (ref "X5") (pin "45") (pinfunction "D16_45") (pintype "passive"))
    )
    (net (code "152") (name "/nstc") (class "Default")
      (node (ref "X3") (pin "78") (pinfunction "nstc_78") (pintype "input"))
      (node (ref "X5") (pin "12") (pinfunction "D29_12") (pintype "passive"))
    )
    (net (code "153") (name "/ovr_0") (class "Default")
      (node (ref "X3") (pin "85") (pinfunction "ovr_0_85") (pintype "input"))
      (node (ref "X5") (pin "4") (pinfunction "D21_4") (pintype "passive"))
    )
    (net (code "154") (name "/ovr_1") (class "Default")
      (node (ref "X3") (pin "102") (pinfunction "ovr_1_102") (pintype "input"))
      (node (ref "X5") (pin "2") (pinfunction "D20_2") (pintype "passive"))
    )
    (net (code "155") (name "/ovr_2") (class "Default")
      (node (ref "X3") (pin "13") (pinfunction "ovr_2_13") (pintype "input"))
      (node (ref "X7") (pin "5") (pinfunction "D23_5") (pintype "passive"))
    )
    (net (code "156") (name "/ovr_3") (class "Default")
      (node (ref "X3") (pin "34") (pinfunction "ovr_3_34") (pintype "input"))
      (node (ref "X7") (pin "3") (pinfunction "D22_3") (pintype "passive"))
    )
    (net (code "157") (name "/sck") (class "Default")
      (node (ref "X3") (pin "54") (pinfunction "sck_54") (pintype "input"))
      (node (ref "X7") (pin "7") (pinfunction "D25_7") (pintype "passive"))
    )
    (net (code "158") (name "/sdi") (class "Default")
      (node (ref "X3") (pin "55") (pinfunction "sdi_55") (pintype "input"))
      (node (ref "X7") (pin "8") (pinfunction "D24_8") (pintype "passive"))
    )
    (net (code "159") (name "/sdo") (class "Default")
      (node (ref "X3") (pin "48") (pinfunction "sdo_48") (pintype "input"))
      (node (ref "X7") (pin "2") (pinfunction "D20_2") (pintype "passive"))
    )
    (net (code "160") (name "/ss") (class "Default")
      (node (ref "X3") (pin "53") (pinfunction "ss_53") (pintype "input"))
      (node (ref "X7") (pin "10") (pinfunction "D26_10") (pintype "passive"))
    )
    (net (code "161") (name "/strob_0") (class "Default")
      (node (ref "X3") (pin "84") (pinfunction "strob_0_84") (pintype "input"))
      (node (ref "X5") (pin "3") (pinfunction "D22_3") (pintype "passive"))
    )
    (net (code "162") (name "/strob_1") (class "Default")
      (node (ref "X3") (pin "83") (pinfunction "strob_1_83") (pintype "input"))
      (node (ref "X5") (pin "5") (pinfunction "D23_5") (pintype "passive"))
    )
    (net (code "163") (name "/strob_2") (class "Default")
      (node (ref "X3") (pin "82") (pinfunction "strob_2_82") (pintype "input"))
      (node (ref "X5") (pin "8") (pinfunction "D24_8") (pintype "passive"))
    )
    (net (code "164") (name "/strob_3") (class "Default")
      (node (ref "X3") (pin "81") (pinfunction "strob_3_81") (pintype "input"))
      (node (ref "X5") (pin "7") (pinfunction "D25_7") (pintype "passive"))
    )
    (net (code "165") (name "/strob_4") (class "Default")
      (node (ref "X3") (pin "80") (pinfunction "strob_4_80") (pintype "input"))
      (node (ref "X5") (pin "10") (pinfunction "D26_10") (pintype "passive"))
    )
    (net (code "166") (name "/strob_5") (class "Default")
      (node (ref "X3") (pin "79") (pinfunction "strob_5_79") (pintype "input"))
      (node (ref "X5") (pin "9") (pinfunction "D27_9") (pintype "passive"))
    )
    (net (code "167") (name "GND") (class "Default")
      (node (ref "C1") (pin "1") (pinfunction "1_1") (pintype "passive"))
      (node (ref "C10") (pin "1") (pinfunction "1_1") (pintype "passive"))
      (node (ref "C11") (pin "1") (pinfunction "1_1") (pintype "passive"))
      (node (ref "C12") (pin "1") (pinfunction "1_1") (pintype "passive"))
      (node (ref "C13") (pin "1") (pinfunction "1_1") (pintype "passive"))
      (node (ref "C2") (pin "1") (pinfunction "1_1") (pintype "passive"))
      (node (ref "C3") (pin "1") (pinfunction "1_1") (pintype "passive"))
      (node (ref "C4") (pin "1") (pinfunction "1_1") (pintype "passive"))
      (node (ref "C5") (pin "1") (pinfunction "1_1") (pintype "passive"))
      (node (ref "C6") (pin "1") (pinfunction "1_1") (pintype "passive"))
      (node (ref "C7") (pin "1") (pinfunction "1_1") (pintype "passive"))
      (node (ref "C8") (pin "1") (pinfunction "1_1") (pintype "passive"))
      (node (ref "C9") (pin "1") (pinfunction "1_1") (pintype "passive"))
      (node (ref "D1") (pin "5") (pinfunction "GND_5") (pintype "passive"))
      (node (ref "D1") (pin "8") (pinfunction "~{EN}_8") (pintype "passive"))
      (node (ref "D2") (pin "5") (pinfunction "GND_5") (pintype "passive"))
      (node (ref "D2") (pin "8") (pinfunction "~{EN}_8") (pintype "passive"))
      (node (ref "D3") (pin "5") (pinfunction "GND_5") (pintype "passive"))
      (node (ref "D3") (pin "8") (pinfunction "~{EN}_8") (pintype "passive"))
      (node (ref "D4") (pin "5") (pinfunction "GND_5") (pintype "passive"))
      (node (ref "D4") (pin "8") (pinfunction "~{EN}_8") (pintype "passive"))
      (node (ref "D5") (pin "5") (pinfunction "GND_5") (pintype "passive"))
      (node (ref "D5") (pin "8") (pinfunction "~{EN}_8") (pintype "passive"))
      (node (ref "D6") (pin "5") (pinfunction "GND_5") (pintype "passive"))
      (node (ref "D6") (pin "8") (pinfunction "~{EN}_8") (pintype "passive"))
      (node (ref "D7") (pin "5") (pinfunction "GND_5") (pintype "passive"))
      (node (ref "D7") (pin "8") (pinfunction "~{EN}_8") (pintype "passive"))
      (node (ref "D8") (pin "5") (pinfunction "GND_5") (pintype "passive"))
      (node (ref "D8") (pin "8") (pinfunction "~{EN}_8") (pintype "passive"))
      (node (ref "P1") (pin "1") (pinfunction "1_1") (pintype "passive"))
      (node (ref "P1") (pin "2") (pinfunction "2_2") (pintype "passive"))
      (node (ref "P2") (pin "1") (pinfunction "1_1") (pintype "passive"))
      (node (ref "P2") (pin "2") (pinfunction "2_2") (pintype "passive"))
      (node (ref "P3") (pin "1") (pinfunction "1_1") (pintype "passive"))
      (node (ref "P3") (pin "2") (pinfunction "2_2") (pintype "passive"))
      (node (ref "P4") (pin "1") (pinfunction "1_1") (pintype "passive"))
      (node (ref "P4") (pin "2") (pinfunction "2_2") (pintype "passive"))
      (node (ref "P5") (pin "1") (pinfunction "1_1") (pintype "passive"))
      (node (ref "P5") (pin "2") (pinfunction "2_2") (pintype "passive"))
      (node (ref "X1") (pin "4") (pinfunction "GND_4") (pintype "passive"))
      (node (ref "X1") (pin "5") (pinfunction "GND_5") (pintype "passive"))
      (node (ref "X1") (pin "6") (pinfunction "GND_6") (pintype "passive"))
      (node (ref "X3") (pin "49") (pinfunction "GND_49") (pintype "input"))
      (node (ref "X3") (pin "51") (pinfunction "GNDio_51") (pintype "input"))
      (node (ref "X4") (pin "4") (pinfunction "GND_4") (pintype "passive"))
      (node (ref "X4") (pin "5") (pinfunction "GND_5") (pintype "passive"))
      (node (ref "X4") (pin "6") (pinfunction "GND_6") (pintype "passive"))
      (node (ref "X5") (pin "1") (pinfunction "GND_1") (pintype "passive"))
      (node (ref "X5") (pin "11") (pinfunction "GND_11") (pintype "passive"))
      (node (ref "X5") (pin "16") (pinfunction "GND_16") (pintype "passive"))
      (node (ref "X5") (pin "21") (pinfunction "GND_21") (pintype "passive"))
      (node (ref "X5") (pin "26") (pinfunction "GND_26") (pintype "passive"))
      (node (ref "X5") (pin "31") (pinfunction "GND_31") (pintype "passive"))
      (node (ref "X5") (pin "36") (pinfunction "GND_36") (pintype "passive"))
      (node (ref "X5") (pin "43") (pinfunction "GND_43") (pintype "passive"))
      (node (ref "X5") (pin "50") (pinfunction "GND_50") (pintype "passive"))
      (node (ref "X5") (pin "6") (pinfunction "GND_6") (pintype "passive"))
      (node (ref "X6") (pin "1") (pinfunction "GND_1") (pintype "passive"))
      (node (ref "X6") (pin "10") (pinfunction "GND_10") (pintype "passive"))
      (node (ref "X6") (pin "13") (pinfunction "GND_13") (pintype "passive"))
      (node (ref "X6") (pin "16") (pinfunction "GND_16") (pintype "passive"))
      (node (ref "X6") (pin "19") (pinfunction "GND_19") (pintype "passive"))
      (node (ref "X6") (pin "22") (pinfunction "GND_22") (pintype "passive"))
      (node (ref "X6") (pin "25") (pinfunction "GND_25") (pintype "passive"))
      (node (ref "X6") (pin "28") (pinfunction "GND_28") (pintype "passive"))
      (node (ref "X6") (pin "31") (pinfunction "GND_31") (pintype "passive"))
      (node (ref "X6") (pin "34") (pinfunction "GND_34") (pintype "passive"))
      (node (ref "X6") (pin "37") (pinfunction "GND_37") (pintype "passive"))
      (node (ref "X6") (pin "4") (pinfunction "GND_4") (pintype "passive"))
      (node (ref "X6") (pin "40") (pinfunction "GND_40") (pintype "passive"))
      (node (ref "X6") (pin "43") (pinfunction "GND_43") (pintype "passive"))
      (node (ref "X6") (pin "45") (pinfunction "GND_45") (pintype "passive"))
      (node (ref "X6") (pin "46") (pinfunction "GND_46") (pintype "passive"))
      (node (ref "X6") (pin "47") (pinfunction "GND_47") (pintype "passive"))
      (node (ref "X6") (pin "48") (pinfunction "GND_48") (pintype "passive"))
      (node (ref "X6") (pin "49") (pinfunction "GND_49") (pintype "passive"))
      (node (ref "X6") (pin "50") (pinfunction "GND_50") (pintype "passive"))
      (node (ref "X6") (pin "7") (pinfunction "GND_7") (pintype "passive"))
      (node (ref "X7") (pin "1") (pinfunction "GND_1") (pintype "passive"))
      (node (ref "X7") (pin "11") (pinfunction "GND_11") (pintype "passive"))
      (node (ref "X7") (pin "16") (pinfunction "GND_16") (pintype "passive"))
      (node (ref "X7") (pin "21") (pinfunction "GND_21") (pintype "passive"))
      (node (ref "X7") (pin "26") (pinfunction "GND_26") (pintype "passive"))
      (node (ref "X7") (pin "31") (pinfunction "GND_31") (pintype "passive"))
      (node (ref "X7") (pin "36") (pinfunction "GND_36") (pintype "passive"))
      (node (ref "X7") (pin "43") (pinfunction "GND_43") (pintype "passive"))
      (node (ref "X7") (pin "50") (pinfunction "GND_50") (pintype "passive"))
      (node (ref "X7") (pin "6") (pinfunction "GND_6") (pintype "passive"))
    )
    (net (code "168") (name "unconnected-(X1-2-Pad3)") (class "Default")
      (node (ref "X1") (pin "3") (pinfunction "2_3") (pintype "passive"))
    )
    (net (code "169") (name "unconnected-(X4-1-Pad2)") (class "Default")
      (node (ref "X4") (pin "2") (pinfunction "1_2") (pintype "passive"))
    )
    (net (code "170") (name "unconnected-(X4-2-Pad3)") (class "Default")
      (node (ref "X4") (pin "3") (pinfunction "2_3") (pintype "passive"))
    )
    (net (code "171") (name "unconnected-(X5-D5-Pad34)") (class "Default")
      (node (ref "X5") (pin "34") (pinfunction "D5_34") (pintype "passive"))
    )
    (net (code "172") (name "unconnected-(X5-D8-Pad38)") (class "Default")
      (node (ref "X5") (pin "38") (pinfunction "D8_38") (pintype "passive"))
    )
    (net (code "173") (name "unconnected-(X5-D10-Pad40)") (class "Default")
      (node (ref "X5") (pin "40") (pinfunction "D10_40") (pintype "passive"))
    )
    (net (code "174") (name "unconnected-(X5-D12-Pad42)") (class "Default")
      (node (ref "X5") (pin "42") (pinfunction "D12_42") (pintype "passive"))
    )
    (net (code "175") (name "unconnected-(X5-D14-Pad44)") (class "Default")
      (node (ref "X5") (pin "44") (pinfunction "D14_44") (pintype "passive"))
    )
    (net (code "176") (name "unconnected-(X5-D15-Pad46)") (class "Default")
      (node (ref "X5") (pin "46") (pinfunction "D15_46") (pintype "passive"))
    )
    (net (code "177") (name "unconnected-(X5-D17-Pad48)") (class "Default")
      (node (ref "X5") (pin "48") (pinfunction "D17_48") (pintype "passive"))
    )
    (net (code "178") (name "unconnected-(X5-D18-Pad47)") (class "Default")
      (node (ref "X5") (pin "47") (pinfunction "D18_47") (pintype "passive"))
    )
    (net (code "179") (name "unconnected-(X5-D19-Pad49)") (class "Default")
      (node (ref "X5") (pin "49") (pinfunction "D19_49") (pintype "passive"))
    )
    (net (code "180") (name "unconnected-(X7-D19-Pad49)") (class "Default")
      (node (ref "X7") (pin "49") (pinfunction "D19_49") (pintype "passive"))
    )
  )
)
